# untitled.net
KiCad netlist of a schematic drawn in EAGLE
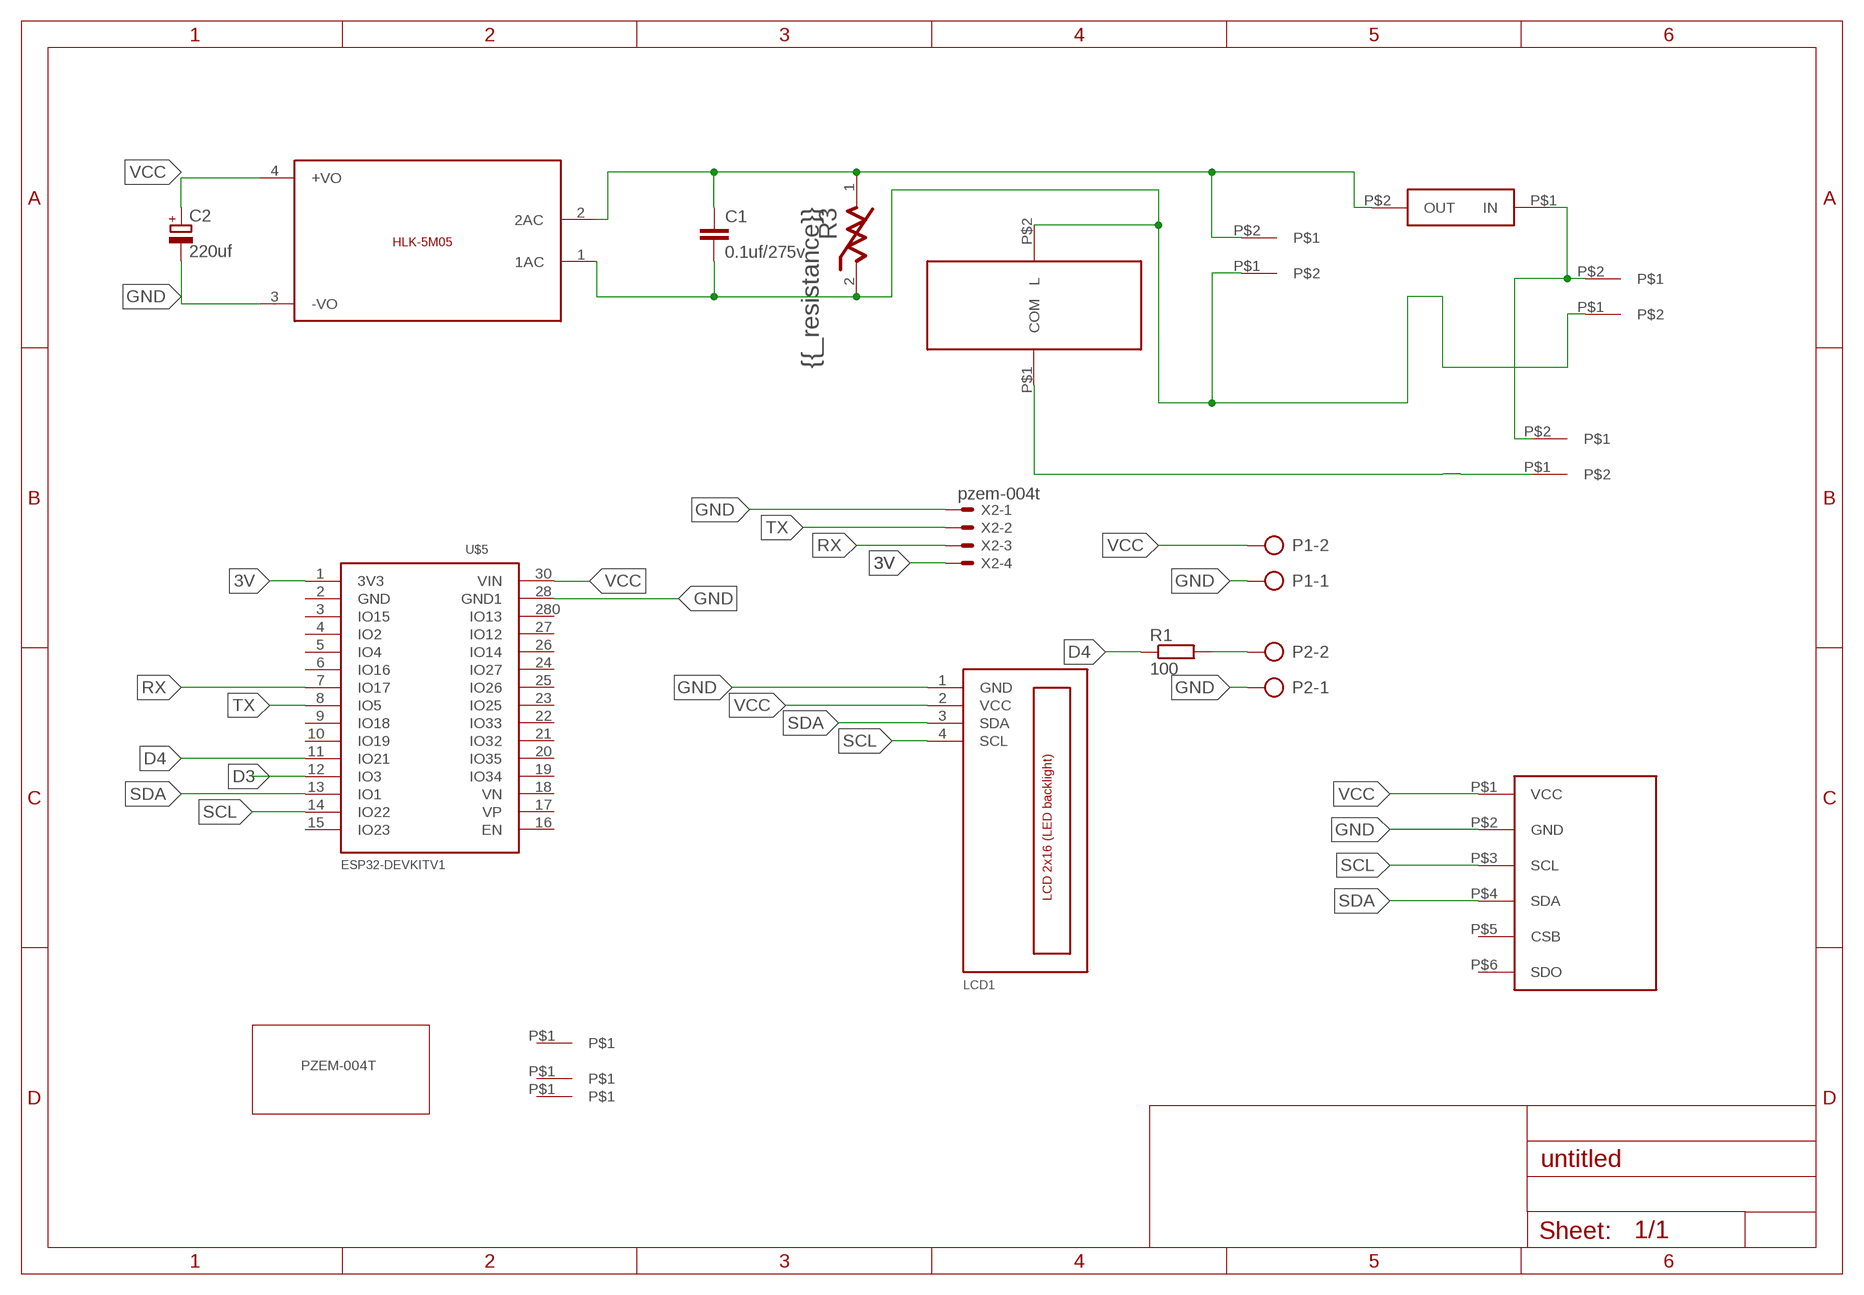
[diagram p0: schematic, sheet 1]

(export (version "E")
  (design (tool "Eeschema 10.0.6"))
  (components
    (comp (ref "1")
      (value "KF76")
      (footprint "eagle-import:KF76")
      (libsource (lib "eagle-import") (part "KF76"))
    )
    (comp (ref "220")
      (value "KF76")
      (footprint "eagle-import:KF76")
      (libsource (lib "eagle-import") (part "KF76"))
    )
    (comp (ref "BME280")
      (value "BMP180")
      (footprint "eagle-import:BPM180")
      (libsource (lib "eagle-import") (part "BMP180"))
    )
    (comp (ref "C1")
      (value "0.1uf/275v")
      (footprint "eagle-import:C7.5B5")
      (libsource (lib "eagle-import") (part "C7.5/5"))
    )
    (comp (ref "C2")
      (value "220uf")
      (footprint "eagle-import:E2-5")
      (libsource (lib "eagle-import") (part "CPOL-EUE2-5"))
    )
    (comp (ref "LCD1")
      (value "LCD_2X16_SIL")
      (footprint "eagle-import:HY-1602F")
      (libsource (lib "eagle-import") (part "LCD_2X16_SIL"))
    )
    (comp (ref "P1")
      (value "AK500/2-H")
      (footprint "eagle-import:AK500_2-H")
      (libsource (lib "eagle-import") (part "AK500/2-H"))
    )
    (comp (ref "P2")
      (value "AK500/2-H")
      (footprint "eagle-import:AK500_2-H")
      (libsource (lib "eagle-import") (part "AK500/2-H"))
    )
    (comp (ref "PZEM")
      (value "KF76")
      (footprint "eagle-import:KF76")
      (libsource (lib "eagle-import") (part "KF76"))
    )
    (comp (ref "R1")
      (value "100")
      (footprint "eagle-import:0207_12")
      (libsource (lib "eagle-import") (part "R-EU_0207/12"))
    )
    (comp (ref "R3")
      (value "10D561K")
      (footprint "eagle-import:BOURNS_INC_MOV-10D471K_0")
      (fields
        (field (name "DIGIKEY_PART_NUMBER") "MOV-10D471K-ND")
        (field (name "MF") "Bourns Inc.")
        (field (name "MOUSER_PART_NUMBER") "652-MOV-10D471K")
      )
      (libsource (lib "eagle-import") (part "BOURNS_INC_MOV-10D471KBOURNS_INC_MOV-10D471K_0_0"))
    )
    (comp (ref "U$1")
      (value "5VDC/5W")
      (footprint "eagle-import:HLK-5M05")
      (libsource (lib "eagle-import") (part "HLK-5M05"))
    )
    (comp (ref "U$2")
      (value "TOROID")
      (footprint "eagle-import:TOROID")
      (libsource (lib "eagle-import") (part "TOROID"))
    )
    (comp (ref "U$3")
      (value "PZEM")
      (footprint "eagle-import:PZEM_FOOTPRINT")
      (libsource (lib "eagle-import") (part "PZEM"))
    )
    (comp (ref "U$4")
      (value "SAPCER")
      (footprint "eagle-import:SPACER")
      (libsource (lib "eagle-import") (part "SAPCER"))
    )
    (comp (ref "U$5")
      (value "ESP32DEVKITV1")
      (footprint "eagle-import:ESP32-DEVKITV1")
      (libsource (lib "eagle-import") (part "ESP32DEVKITV1"))
    )
    (comp (ref "U$6")
      (value "SAPCER")
      (footprint "eagle-import:SPACER")
      (libsource (lib "eagle-import") (part "SAPCER"))
    )
    (comp (ref "U$7")
      (value "SAPCER")
      (footprint "eagle-import:SPACER")
      (libsource (lib "eagle-import") (part "SAPCER"))
    )
    (comp (ref "U$8")
      (value "FUSE")
      (footprint "eagle-import:FUSE")
      (libsource (lib "eagle-import") (part "FUSE"))
    )
    (comp (ref "X2")
      (value "pzem-004t")
      (footprint "eagle-import:22-23-2041")
      (fields (field (name "MF") "MOLEX") (field (name "MPN") "22-23-2041"))
      (libsource (lib "eagle-import") (part "22-23-2041"))
    )
  )
  (nets
    (net (code "1") (name "3V") (class "Default")
      (node (ref "U$5") (pin "1") (pinfunction "3V3_1") (pintype "bidirectional"))
      (node (ref "X2") (pin "4") (pinfunction "S_4") (pintype "passive"))
    )
    (net (code "2") (name "D3") (class "Default")
      (node (ref "U$5") (pin "12") (pinfunction "IO3_12") (pintype "bidirectional"))
    )
    (net (code "3") (name "D4") (class "Default")
      (node (ref "R1") (pin "1") (pinfunction "1_1") (pintype "passive"))
      (node (ref "U$5") (pin "11") (pinfunction "IO21_11") (pintype "bidirectional"))
    )
    (net (code "4") (name "GND") (class "Default")
      (node (ref "BME280") (pin "P$2") (pinfunction "GND_P$2") (pintype "bidirectional"))
      (node (ref "C2") (pin "-") (pinfunction "-_-") (pintype "passive"))
      (node (ref "LCD1") (pin "1") (pinfunction "GND_1") (pintype "power_in"))
      (node (ref "P1") (pin "1") (pinfunction "KL_1") (pintype "passive"))
      (node (ref "P2") (pin "1") (pinfunction "KL_1") (pintype "passive"))
      (node (ref "U$1") (pin "3") (pinfunction "-VO_3") (pintype "bidirectional"))
      (node (ref "U$5") (pin "28") (pinfunction "GND1_28") (pintype "bidirectional"))
      (node (ref "X2") (pin "1") (pinfunction "S_1") (pintype "passive"))
    )
    (net (code "5") (name "Net-(1-P$1)") (class "Default")
      (node (ref "1") (pin "P$2") (pinfunction "P$1_P$2") (pintype "bidirectional"))
      (node (ref "220") (pin "P$2") (pinfunction "P$1_P$2") (pintype "bidirectional"))
      (node (ref "U$8") (pin "P$1") (pinfunction "IN_P$1") (pintype "bidirectional"))
    )
    (net (code "6") (name "Net-(1-P$2)") (class "Default")
      (node (ref "1") (pin "P$1") (pinfunction "P$2_P$1") (pintype "bidirectional"))
      (node (ref "U$2") (pin "P$1") (pinfunction "COM_P$1") (pintype "bidirectional"))
    )
    (net (code "7") (name "Net-(220-P$2)") (class "Default")
      (node (ref "220") (pin "P$1") (pinfunction "P$2_P$1") (pintype "bidirectional"))
      (node (ref "C1") (pin "2") (pinfunction "2_2") (pintype "passive"))
      (node (ref "PZEM") (pin "P$1") (pinfunction "P$2_P$1") (pintype "bidirectional"))
      (node (ref "R3") (pin "2") (pinfunction "2_2") (pintype "passive"))
      (node (ref "U$1") (pin "1") (pinfunction "1AC_1") (pintype "bidirectional"))
      (node (ref "U$2") (pin "P$2") (pinfunction "L_P$2") (pintype "bidirectional"))
    )
    (net (code "8") (name "Net-(P2B-KL)") (class "Default")
      (node (ref "P2") (pin "2") (pinfunction "KL_2") (pintype "passive"))
      (node (ref "R1") (pin "2") (pinfunction "2_2") (pintype "passive"))
    )
    (net (code "9") (name "Net-(PZEM-P$1)") (class "Default")
      (node (ref "C1") (pin "1") (pinfunction "1_1") (pintype "passive"))
      (node (ref "PZEM") (pin "P$2") (pinfunction "P$1_P$2") (pintype "bidirectional"))
      (node (ref "R3") (pin "1") (pinfunction "1_1") (pintype "passive"))
      (node (ref "U$1") (pin "2") (pinfunction "2AC_2") (pintype "bidirectional"))
      (node (ref "U$8") (pin "P$2") (pinfunction "OUT_P$2") (pintype "bidirectional"))
    )
    (net (code "10") (name "RX") (class "Default")
      (node (ref "U$5") (pin "7") (pinfunction "IO17_7") (pintype "bidirectional"))
      (node (ref "X2") (pin "3") (pinfunction "S_3") (pintype "passive"))
    )
    (net (code "11") (name "SCL") (class "Default")
      (node (ref "BME280") (pin "P$3") (pinfunction "SCL_P$3") (pintype "bidirectional"))
      (node (ref "LCD1") (pin "4") (pinfunction "SCL_4") (pintype "input"))
      (node (ref "U$5") (pin "14") (pinfunction "IO22_14") (pintype "bidirectional"))
    )
    (net (code "12") (name "SDA") (class "Default")
      (node (ref "BME280") (pin "P$4") (pinfunction "SDA_P$4") (pintype "bidirectional"))
      (node (ref "LCD1") (pin "3") (pinfunction "SDA_3") (pintype "input"))
      (node (ref "U$5") (pin "13") (pinfunction "IO1_13") (pintype "bidirectional"))
    )
    (net (code "13") (name "TX") (class "Default")
      (node (ref "U$5") (pin "8") (pinfunction "IO5_8") (pintype "bidirectional"))
      (node (ref "X2") (pin "2") (pinfunction "S_2") (pintype "passive"))
    )
    (net (code "14") (name "VCC") (class "Default")
      (node (ref "BME280") (pin "P$1") (pinfunction "VCC_P$1") (pintype "bidirectional"))
      (node (ref "C2") (pin "+") (pinfunction "+_+") (pintype "passive"))
      (node (ref "LCD1") (pin "2") (pinfunction "VCC_2") (pintype "power_in"))
      (node (ref "P1") (pin "2") (pinfunction "KL_2") (pintype "passive"))
      (node (ref "U$1") (pin "4") (pinfunction "+VO_4") (pintype "bidirectional"))
      (node (ref "U$5") (pin "30") (pinfunction "VIN_30") (pintype "bidirectional"))
    )
    (net (code "15") (name "unconnected-(BME280-CSB-PadP$5)") (class "Default")
      (node (ref "BME280") (pin "P$5") (pinfunction "CSB_P$5") (pintype "bidirectional"))
    )
    (net (code "16") (name "unconnected-(BME280-SDO-PadP$6)") (class "Default")
      (node (ref "BME280") (pin "P$6") (pinfunction "SDO_P$6") (pintype "bidirectional"))
    )
    (net (code "17") (name "unconnected-(U$4-PadP$1)") (class "Default")
      (node (ref "U$4") (pin "P$1") (pinfunction "P$1_P$1") (pintype "bidirectional"))
    )
    (net (code "18") (name "unconnected-(U$5-EN-Pad16)") (class "Default")
      (node (ref "U$5") (pin "16") (pinfunction "EN_16") (pintype "bidirectional"))
    )
    (net (code "19") (name "unconnected-(U$5-GND-Pad2)") (class "Default")
      (node (ref "U$5") (pin "2") (pinfunction "GND_2") (pintype "bidirectional"))
    )
    (net (code "20") (name "unconnected-(U$5-IO2-Pad4)") (class "Default")
      (node (ref "U$5") (pin "4") (pinfunction "IO2_4") (pintype "bidirectional"))
    )
    (net (code "21") (name "unconnected-(U$5-IO4-Pad5)") (class "Default")
      (node (ref "U$5") (pin "5") (pinfunction "IO4_5") (pintype "bidirectional"))
    )
    (net (code "22") (name "unconnected-(U$5-IO12-Pad27)") (class "Default")
      (node (ref "U$5") (pin "27") (pinfunction "IO12_27") (pintype "bidirectional"))
    )
    (net (code "23") (name "unconnected-(U$5-IO13-Pad280)") (class "Default")
      (node (ref "U$5") (pin "280") (pinfunction "IO13_280") (pintype "bidirectional"))
    )
    (net (code "24") (name "unconnected-(U$5-IO14-Pad26)") (class "Default")
      (node (ref "U$5") (pin "26") (pinfunction "IO14_26") (pintype "bidirectional"))
    )
    (net (code "25") (name "unconnected-(U$5-IO15-Pad3)") (class "Default")
      (node (ref "U$5") (pin "3") (pinfunction "IO15_3") (pintype "bidirectional"))
    )
    (net (code "26") (name "unconnected-(U$5-IO16-Pad6)") (class "Default")
      (node (ref "U$5") (pin "6") (pinfunction "IO16_6") (pintype "bidirectional"))
    )
    (net (code "27") (name "unconnected-(U$5-IO18-Pad9)") (class "Default")
      (node (ref "U$5") (pin "9") (pinfunction "IO18_9") (pintype "bidirectional"))
    )
    (net (code "28") (name "unconnected-(U$5-IO19-Pad10)") (class "Default")
      (node (ref "U$5") (pin "10") (pinfunction "IO19_10") (pintype "bidirectional"))
    )
    (net (code "29") (name "unconnected-(U$5-IO23-Pad15)") (class "Default")
      (node (ref "U$5") (pin "15") (pinfunction "IO23_15") (pintype "bidirectional"))
    )
    (net (code "30") (name "unconnected-(U$5-IO25-Pad23)") (class "Default")
      (node (ref "U$5") (pin "23") (pinfunction "IO25_23") (pintype "bidirectional"))
    )
    (net (code "31") (name "unconnected-(U$5-IO26-Pad25)") (class "Default")
      (node (ref "U$5") (pin "25") (pinfunction "IO26_25") (pintype "bidirectional"))
    )
    (net (code "32") (name "unconnected-(U$5-IO27-Pad24)") (class "Default")
      (node (ref "U$5") (pin "24") (pinfunction "IO27_24") (pintype "bidirectional"))
    )
    (net (code "33") (name "unconnected-(U$5-IO32-Pad21)") (class "Default")
      (node (ref "U$5") (pin "21") (pinfunction "IO32_21") (pintype "bidirectional"))
    )
    (net (code "34") (name "unconnected-(U$5-IO33-Pad22)") (class "Default")
      (node (ref "U$5") (pin "22") (pinfunction "IO33_22") (pintype "bidirectional"))
    )
    (net (code "35") (name "unconnected-(U$5-IO34-Pad19)") (class "Default")
      (node (ref "U$5") (pin "19") (pinfunction "IO34_19") (pintype "bidirectional"))
    )
    (net (code "36") (name "unconnected-(U$5-IO35-Pad20)") (class "Default")
      (node (ref "U$5") (pin "20") (pinfunction "IO35_20") (pintype "bidirectional"))
    )
    (net (code "37") (name "unconnected-(U$5-VN-Pad18)") (class "Default")
      (node (ref "U$5") (pin "18") (pinfunction "VN_18") (pintype "bidirectional"))
    )
    (net (code "38") (name "unconnected-(U$5-VP-Pad17)") (class "Default")
      (node (ref "U$5") (pin "17") (pinfunction "VP_17") (pintype "bidirectional"))
    )
    (net (code "39") (name "unconnected-(U$6-PadP$1)") (class "Default")
      (node (ref "U$6") (pin "P$1") (pinfunction "P$1_P$1") (pintype "bidirectional"))
    )
    (net (code "40") (name "unconnected-(U$7-PadP$1)") (class "Default")
      (node (ref "U$7") (pin "P$1") (pinfunction "P$1_P$1") (pintype "bidirectional"))
    )
  )
)
